# d_00_e_01.net
KiCad netlist of a schematic drawn in EasyEDA
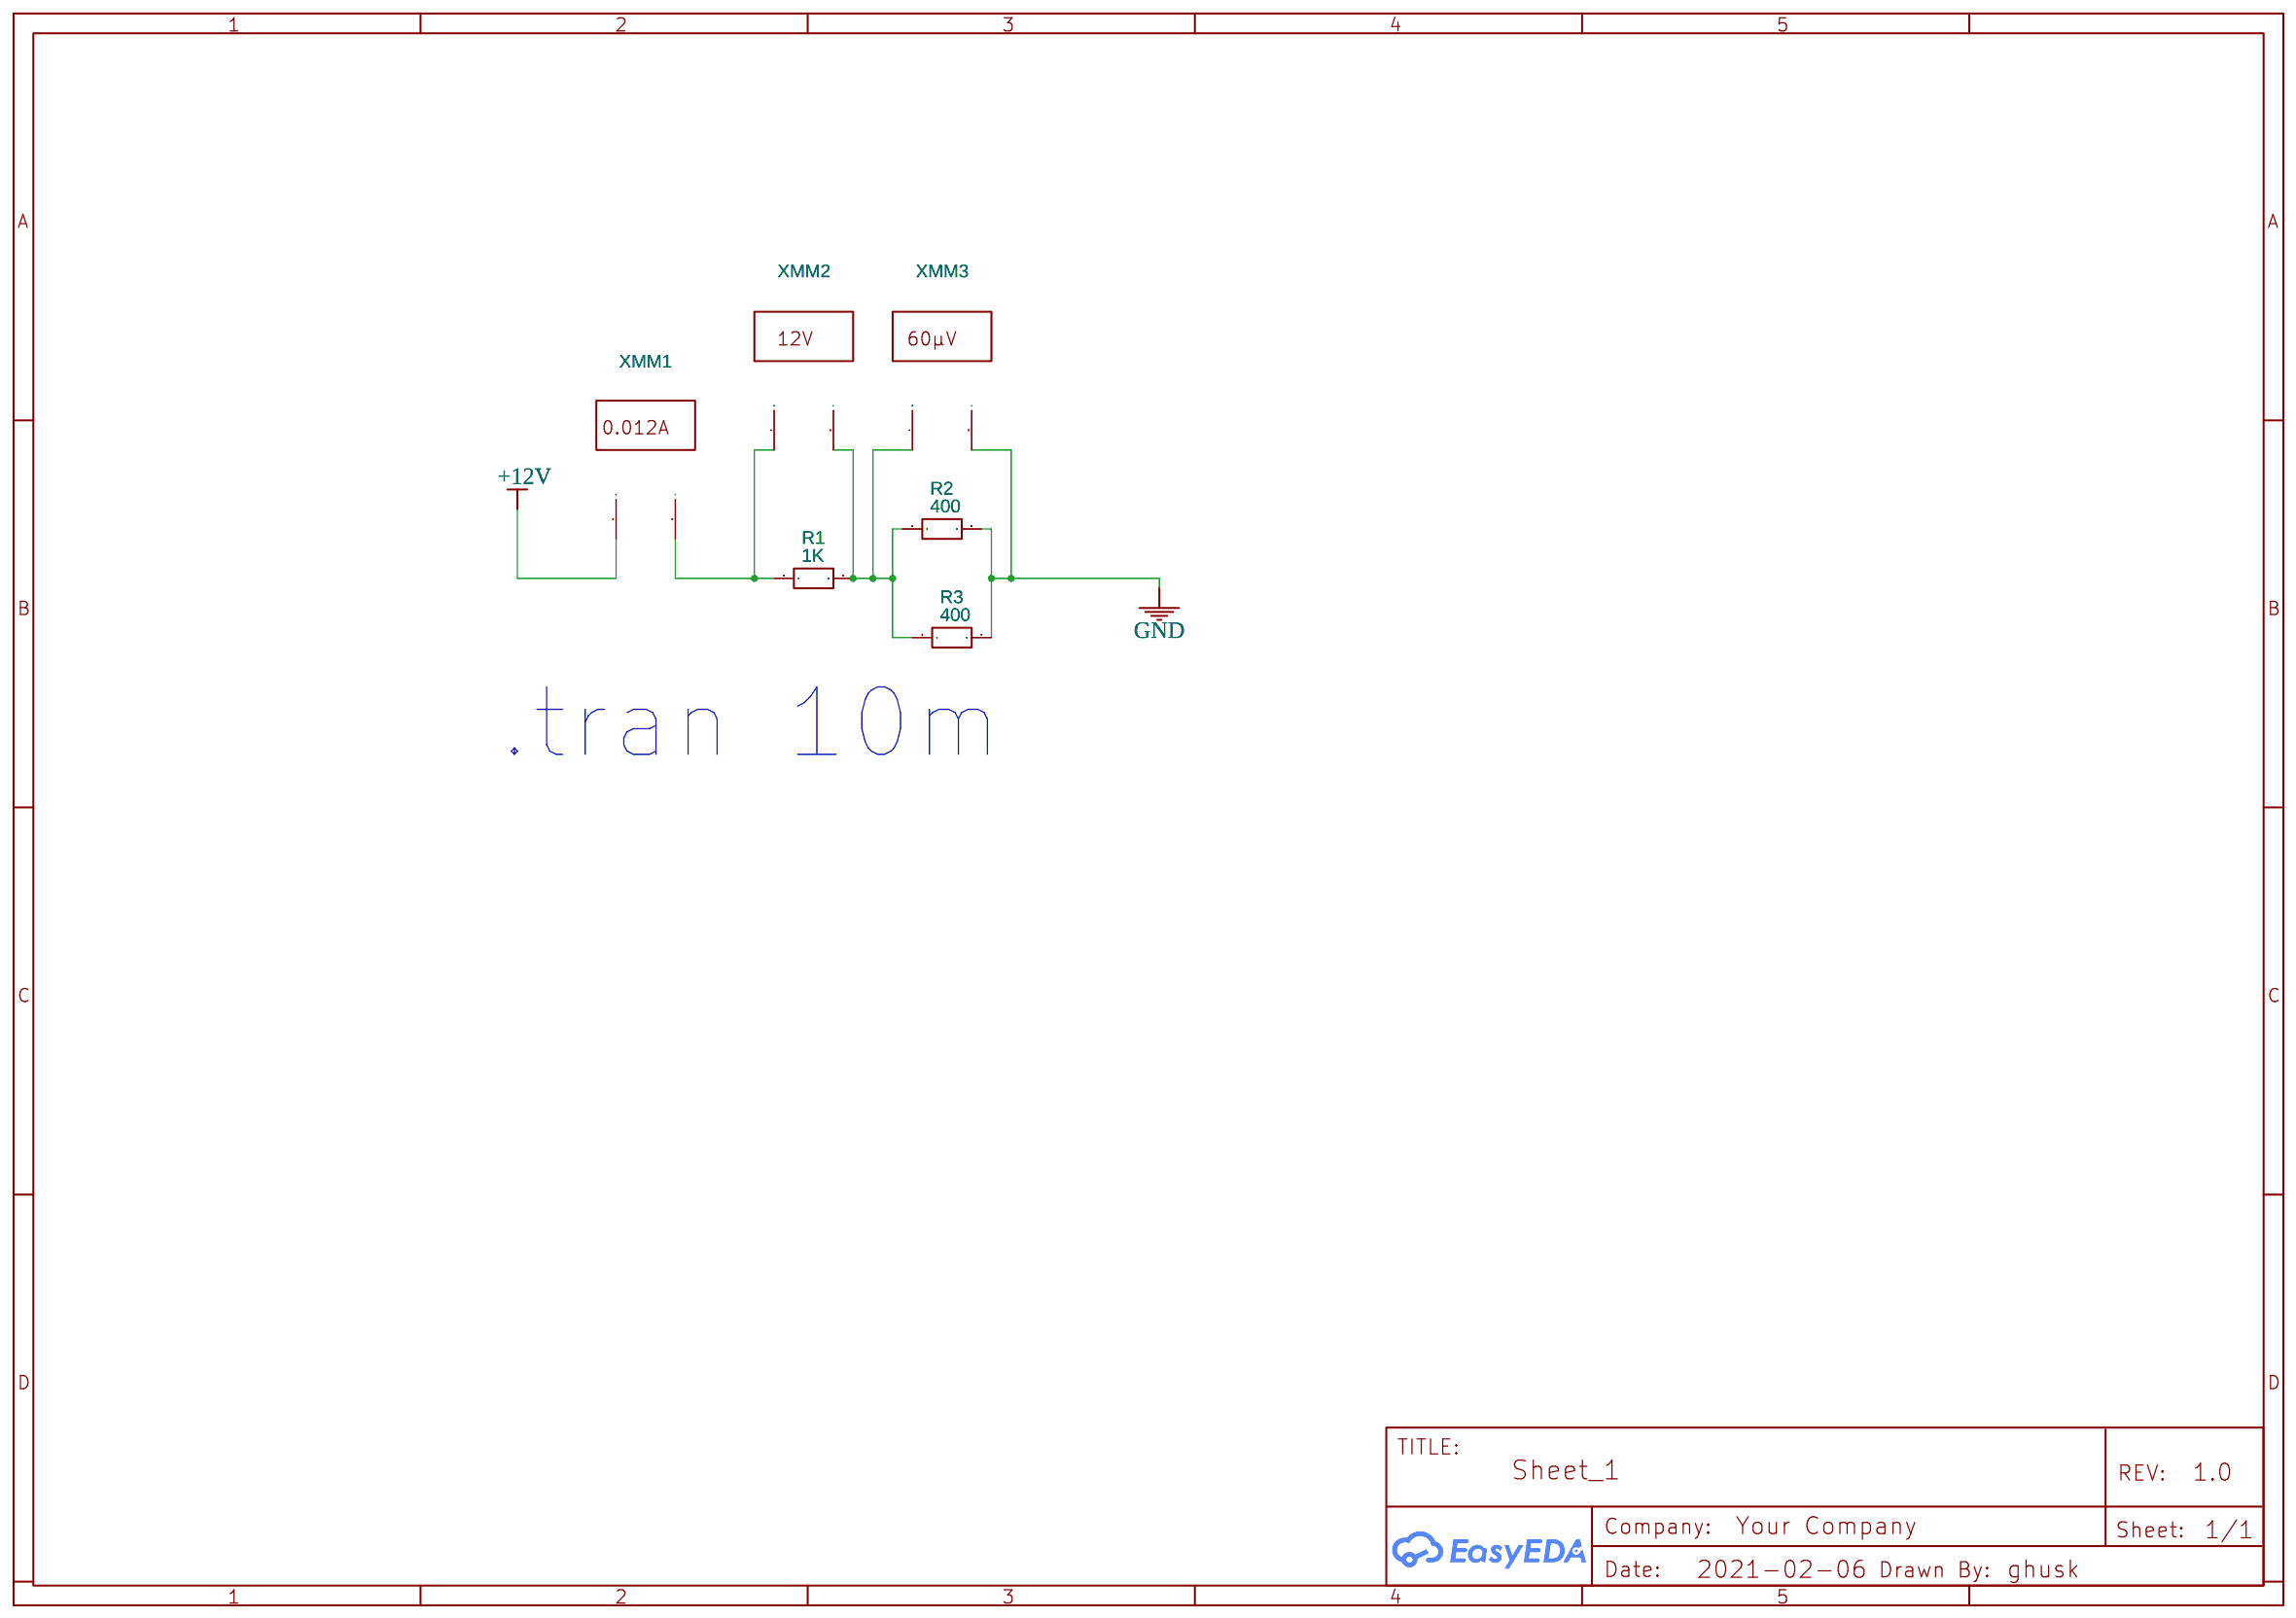
[diagram p0: schematic sheet]

(export (version "E")
  (design (tool "Eeschema 10.0.6"))
  (components
    (comp (ref "R1") (value "1K") (libsource (lib "") (part "Resistor_EU")))
    (comp (ref "R2") (value "400") (libsource (lib "") (part "Resistor_EU")))
    (comp (ref "R3") (value "400") (libsource (lib "") (part "Resistor_EU")))
    (comp (ref "XMM1") (value "Multimeter") (libsource (lib "") (part "MULTIMETER_1")))
    (comp (ref "XMM2") (value "Multimeter") (libsource (lib "") (part "MULTIMETER")))
    (comp (ref "XMM3") (value "Multimeter") (libsource (lib "") (part "MULTIMETER_2")))
  )
  (nets
    (net (code "1") (name "+12V") (class "Default")
      (node (ref "XMM1") (pin "1") (pinfunction "+_1") (pintype "unspecified"))
    )
    (net (code "2") (name "GND") (class "Default")
      (node (ref "R2") (pin "2") (pinfunction "2_2") (pintype "unspecified"))
      (node (ref "R3") (pin "2") (pinfunction "2_2") (pintype "unspecified"))
      (node (ref "XMM3") (pin "2") (pinfunction "I_2") (pintype "unspecified"))
    )
    (net (code "3") (name "Net-(XMM1-I)") (class "Default")
      (node (ref "R1") (pin "1") (pinfunction "1_1") (pintype "unspecified"))
      (node (ref "XMM1") (pin "2") (pinfunction "I_2") (pintype "unspecified"))
      (node (ref "XMM2") (pin "1") (pinfunction "+_1") (pintype "unspecified"))
    )
    (net (code "4") (name "Net-(XMM2-I)") (class "Default")
      (node (ref "R1") (pin "2") (pinfunction "2_2") (pintype "unspecified"))
      (node (ref "R2") (pin "1") (pinfunction "1_1") (pintype "unspecified"))
      (node (ref "R3") (pin "1") (pinfunction "1_1") (pintype "unspecified"))
      (node (ref "XMM2") (pin "2") (pinfunction "I_2") (pintype "unspecified"))
      (node (ref "XMM3") (pin "1") (pinfunction "+_1") (pintype "unspecified"))
    )
  )
)
